# design.net
KiCad netlist of a schematic drawn in Altium Designer
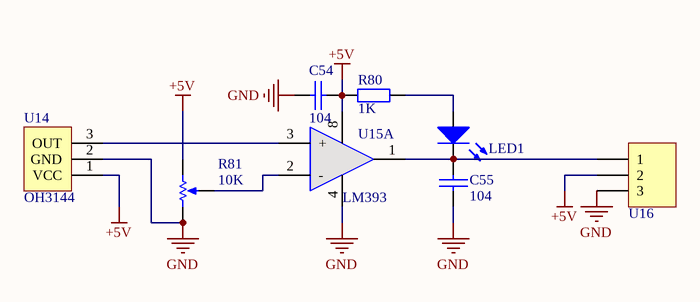
[diagram p0: 转速检测.SchDoc]

(export (version "E")
  (design (tool "Eeschema 10.0.6"))
  (components
    (comp (ref "C54")
      (value "104")
      (footprint "0603C")
      (description "安规电容")
      (libsource (lib "MY_Library") (part "CAP X"))
    )
    (comp (ref "C55")
      (value "104")
      (footprint "0603C")
      (description "安规电容")
      (libsource (lib "MY_Library") (part "CAP X"))
    )
    (comp (ref "LED1") (value "COLOUR") (footprint "0603LED") (libsource (lib "MY_Library") (part "ledφ6")))
    (comp (ref "R80")
      (value "1K")
      (footprint "0603-1")
      (description "贴片电阻")
      (fields (field (name "Comment") "Res1") (field (name "PUBLISHER") "Altium Limited"))
      (libsource (lib "Fszhang") (part "Res1"))
    )
    (comp (ref "R81")
      (value "10K")
      (footprint "3x3dianweiqi")
      (description "精密可调电阻")
      (fields (field (name "Comment") "RPot") (field (name "PUBLISHER") "Altium Limited"))
      (libsource (lib "Fszhang") (part "RPot"))
    )
    (comp (ref "U14")
      (value "OH3144")
      (footprint "OH3144")
      (description "国产霍尔开关")
      (libsource (lib "Fszhang") (part "OH3144"))
    )
    (comp (ref "U15")
      (value "LM393")
      (footprint "NSO8_N")
      (description "比较器")
      (libsource (lib "Fszhang") (part "LM393"))
    )
    (comp (ref "U16")
      (value "Header 3")
      (footprint "HDR3X1_A")
      (description "接插件")
      (fields (field (name "PUBLISHER") "Altium Limited"))
      (libsource (lib "Fszhang") (part "Header 3"))
    )
  )
  (nets
    (net (code "1") (name "+5V") (class "Default")
      (node (ref "C54") (pin "2") (pinfunction "2_2") (pintype "passive"))
      (node (ref "R80") (pin "1") (pinfunction "1_1") (pintype "passive"))
      (node (ref "R81") (pin "3") (pinfunction "BOT_3") (pintype "passive"))
      (node (ref "U14") (pin "1") (pinfunction "VCC_1") (pintype "passive"))
      (node (ref "U15") (pin "8") (pinfunction "V+_8") (pintype "power_in"))
      (node (ref "U16") (pin "2") (pinfunction "2_2") (pintype "passive"))
    )
    (net (code "2") (name "GND") (class "Default")
      (node (ref "C54") (pin "1") (pinfunction "1_1") (pintype "passive"))
      (node (ref "C55") (pin "1") (pinfunction "1_1") (pintype "passive"))
      (node (ref "R81") (pin "1") (pinfunction "TOP_1") (pintype "passive"))
      (node (ref "U14") (pin "2") (pinfunction "GND_2") (pintype "passive"))
      (node (ref "U15") (pin "4") (pinfunction "V-_4") (pintype "power_in"))
      (node (ref "U16") (pin "3") (pinfunction "3_3") (pintype "passive"))
    )
    (net (code "3") (name "Net-(LED1-+)") (class "Default")
      (node (ref "LED1") (pin "1") (pinfunction "+_1") (pintype "passive"))
      (node (ref "R80") (pin "2") (pinfunction "2_2") (pintype "passive"))
    )
    (net (code "4") (name "Net-(LED1--)") (class "Default")
      (node (ref "C55") (pin "2") (pinfunction "2_2") (pintype "passive"))
      (node (ref "LED1") (pin "2") (pinfunction "-_2") (pintype "passive"))
      (node (ref "U15") (pin "1") (pinfunction "OUT1_1") (pintype "passive"))
      (node (ref "U16") (pin "1") (pinfunction "1_1") (pintype "passive"))
    )
    (net (code "5") (name "Net-(R81-TAP)") (class "Default")
      (node (ref "R81") (pin "2") (pinfunction "TAP_2") (pintype "passive"))
      (node (ref "U15") (pin "2") (pinfunction "-_2") (pintype "passive"))
    )
    (net (code "6") (name "Net-(U14-OUT)") (class "Default")
      (node (ref "U14") (pin "3") (pinfunction "OUT_3") (pintype "passive"))
      (node (ref "U15") (pin "3") (pinfunction "+_3") (pintype "passive"))
    )
  )
)
